# 4_Digitrol.net
KiCad netlist of a schematic drawn in Altium Designer
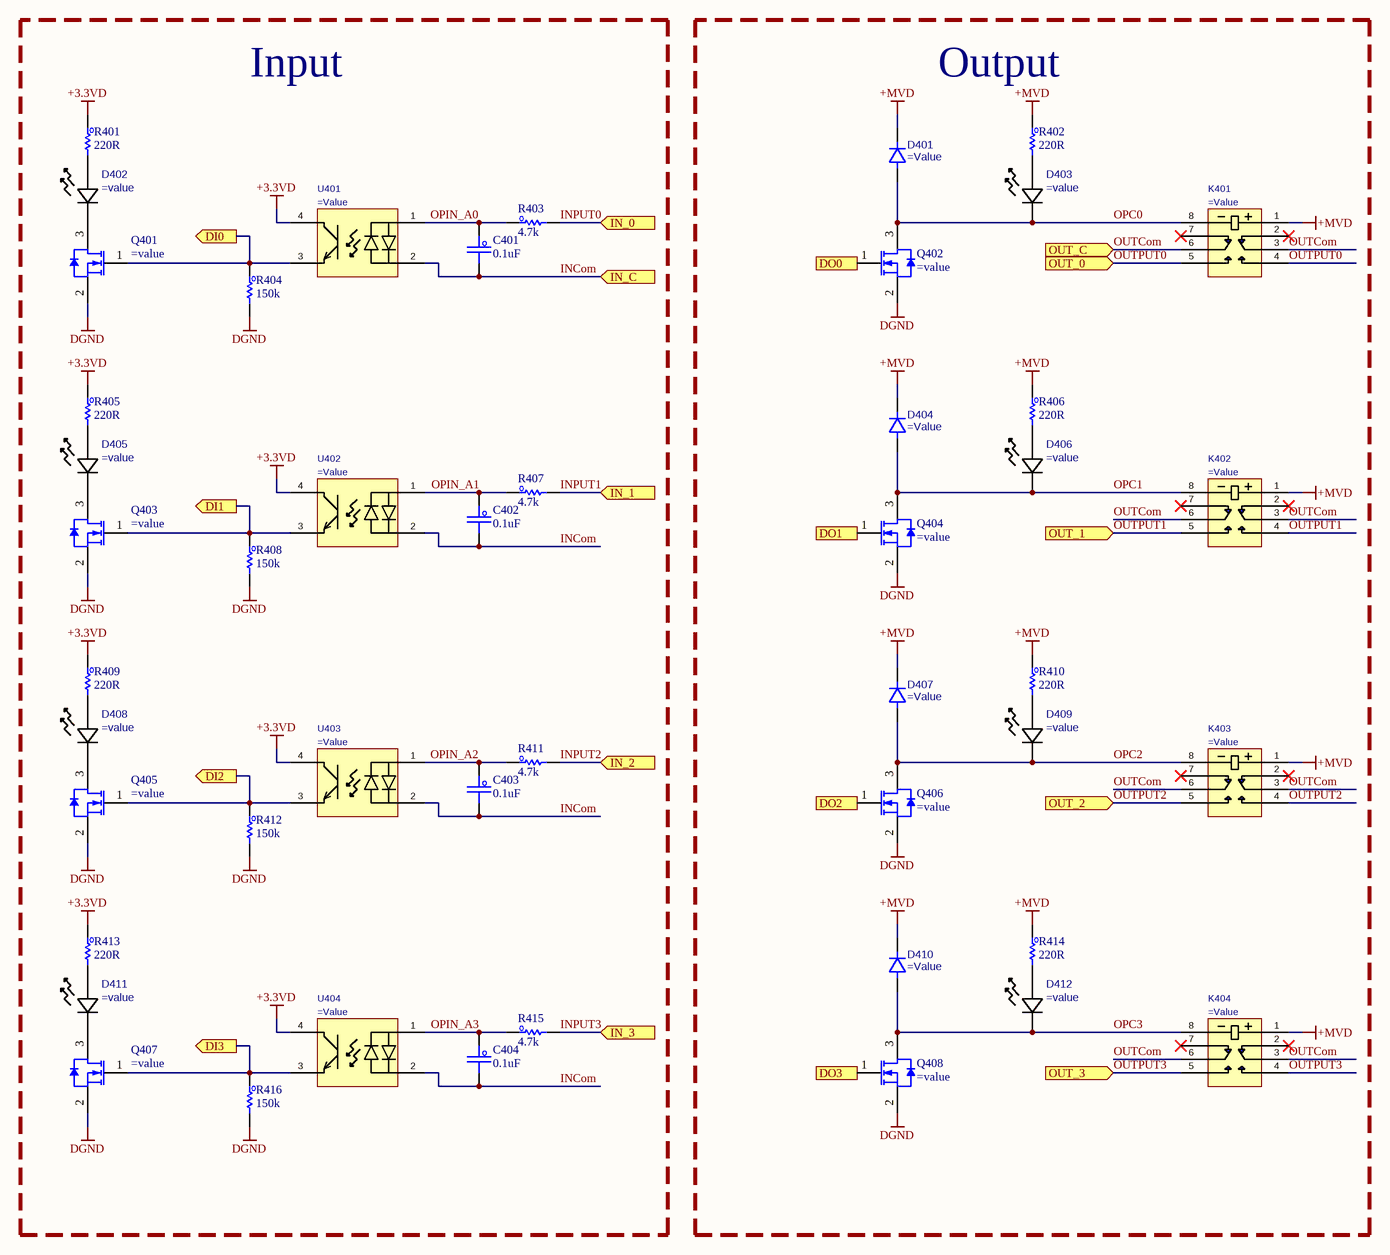
[diagram p0: 4_Digitrol.SchDoc]

(export (version "E")
  (design (tool "Eeschema 10.0.6"))
  (components
    (comp (ref "C401")
      (value "0.1uF")
      (footprint "C_0603")
      (description "CAP CER 0.1UF 50V X7R 0603")
      (fields (field (name "MANUFACTURER") "KEMET") (field (name "PARTNUMBER") "C0603C104K5RACTU"))
      (libsource (lib "UUSymbol") (part "C_Capacitor"))
    )
    (comp (ref "C402")
      (value "0.1uF")
      (footprint "C_0603")
      (description "CAP CER 0.1UF 50V X7R 0603")
      (fields (field (name "MANUFACTURER") "KEMET") (field (name "PARTNUMBER") "C0603C104K5RACTU"))
      (libsource (lib "UUSymbol") (part "C_Capacitor"))
    )
    (comp (ref "C403")
      (value "0.1uF")
      (footprint "C_0603")
      (description "CAP CER 0.1UF 50V X7R 0603")
      (fields (field (name "MANUFACTURER") "KEMET") (field (name "PARTNUMBER") "C0603C104K5RACTU"))
      (libsource (lib "UUSymbol") (part "C_Capacitor"))
    )
    (comp (ref "C404")
      (value "0.1uF")
      (footprint "C_0603")
      (description "CAP CER 0.1UF 50V X7R 0603")
      (fields (field (name "MANUFACTURER") "KEMET") (field (name "PARTNUMBER") "C0603C104K5RACTU"))
      (libsource (lib "UUSymbol") (part "C_Capacitor"))
    )
    (comp (ref "D401")
      (value "~")
      (footprint "SOD323")
      (description "DIODE SCHOTTKY 40V 2A 0603")
      (fields (field (name "MANUFACTURER") "Slkor(SLKORMICRO Elec.)") (field (name "PARTNUMBER") "SD103AWS"))
      (libsource (lib "UUSymbol") (part "D_PW_SD103AWS"))
    )
    (comp (ref "D402")
      (value "~")
      (footprint "LED_0VS75000_WRE")
      (description "LED BLUE CLEAR 0603 SMD")
      (fields (field (name "MANUFACTURER") "Wurth Electronics") (field (name "PARTNUMBER") "150060VS75000"))
      (libsource (lib "UUSymbol") (part "D_LED_150060BS75000"))
    )
    (comp (ref "D403")
      (value "~")
      (footprint "LED_0VS75000_WRE")
      (description "LED BLUE CLEAR 0603 SMD")
      (fields (field (name "MANUFACTURER") "Wurth Electronics") (field (name "PARTNUMBER") "150060VS75000"))
      (libsource (lib "UUSymbol") (part "D_LED_150060BS75000"))
    )
    (comp (ref "D404")
      (value "~")
      (footprint "SOD323")
      (description "DIODE SCHOTTKY 40V 2A 0603")
      (fields (field (name "MANUFACTURER") "Slkor(SLKORMICRO Elec.)") (field (name "PARTNUMBER") "SD103AWS"))
      (libsource (lib "UUSymbol") (part "D_PW_SD103AWS"))
    )
    (comp (ref "D405")
      (value "~")
      (footprint "LED_0VS75000_WRE")
      (description "LED BLUE CLEAR 0603 SMD")
      (fields (field (name "MANUFACTURER") "Wurth Electronics") (field (name "PARTNUMBER") "150060VS75000"))
      (libsource (lib "UUSymbol") (part "D_LED_150060BS75000"))
    )
    (comp (ref "D406")
      (value "~")
      (footprint "LED_0VS75000_WRE")
      (description "LED BLUE CLEAR 0603 SMD")
      (fields (field (name "MANUFACTURER") "Wurth Electronics") (field (name "PARTNUMBER") "150060VS75000"))
      (libsource (lib "UUSymbol") (part "D_LED_150060BS75000"))
    )
    (comp (ref "D407")
      (value "~")
      (footprint "SOD323")
      (description "DIODE SCHOTTKY 40V 2A 0603")
      (fields (field (name "MANUFACTURER") "Slkor(SLKORMICRO Elec.)") (field (name "PARTNUMBER") "SD103AWS"))
      (libsource (lib "UUSymbol") (part "D_PW_SD103AWS"))
    )
    (comp (ref "D408")
      (value "~")
      (footprint "LED_0VS75000_WRE")
      (description "LED BLUE CLEAR 0603 SMD")
      (fields (field (name "MANUFACTURER") "Wurth Electronics") (field (name "PARTNUMBER") "150060VS75000"))
      (libsource (lib "UUSymbol") (part "D_LED_150060BS75000"))
    )
    (comp (ref "D409")
      (value "~")
      (footprint "LED_0VS75000_WRE")
      (description "LED BLUE CLEAR 0603 SMD")
      (fields (field (name "MANUFACTURER") "Wurth Electronics") (field (name "PARTNUMBER") "150060VS75000"))
      (libsource (lib "UUSymbol") (part "D_LED_150060BS75000"))
    )
    (comp (ref "D410")
      (value "~")
      (footprint "SOD323")
      (description "DIODE SCHOTTKY 40V 2A 0603")
      (fields (field (name "MANUFACTURER") "Slkor(SLKORMICRO Elec.)") (field (name "PARTNUMBER") "SD103AWS"))
      (libsource (lib "UUSymbol") (part "D_PW_SD103AWS"))
    )
    (comp (ref "D411")
      (value "~")
      (footprint "LED_0VS75000_WRE")
      (description "LED BLUE CLEAR 0603 SMD")
      (fields (field (name "MANUFACTURER") "Wurth Electronics") (field (name "PARTNUMBER") "150060VS75000"))
      (libsource (lib "UUSymbol") (part "D_LED_150060BS75000"))
    )
    (comp (ref "D412")
      (value "~")
      (footprint "LED_0VS75000_WRE")
      (description "LED BLUE CLEAR 0603 SMD")
      (fields (field (name "MANUFACTURER") "Wurth Electronics") (field (name "PARTNUMBER") "150060VS75000"))
      (libsource (lib "UUSymbol") (part "D_LED_150060BS75000"))
    )
    (comp (ref "K401")
      (value "~")
      (footprint "RELAY_HFD4/12-SR")
      (description "Telecom Non Latching 12VDC DPDT SMD Relays RoHS")
      (fields
        (field (name "MANUFACTURER") "Xiamen Hongfa Electroacoustic")
        (field (name "PARTNUMBER") "HFD4/5-SR")
      )
      (libsource (lib "UUSymbol") (part "SW_RELAY_HFD4/12-SR"))
    )
    (comp (ref "K402")
      (value "~")
      (footprint "RELAY_HFD4/12-SR")
      (description "Telecom Non Latching 12VDC DPDT SMD Relays RoHS")
      (fields
        (field (name "MANUFACTURER") "Xiamen Hongfa Electroacoustic")
        (field (name "PARTNUMBER") "HFD4/5-SR")
      )
      (libsource (lib "UUSymbol") (part "SW_RELAY_HFD4/12-SR"))
    )
    (comp (ref "K403")
      (value "~")
      (footprint "RELAY_HFD4/12-SR")
      (description "Telecom Non Latching 12VDC DPDT SMD Relays RoHS")
      (fields
        (field (name "MANUFACTURER") "Xiamen Hongfa Electroacoustic")
        (field (name "PARTNUMBER") "HFD4/5-SR")
      )
      (libsource (lib "UUSymbol") (part "SW_RELAY_HFD4/12-SR"))
    )
    (comp (ref "K404")
      (value "~")
      (footprint "RELAY_HFD4/12-SR")
      (description "Telecom Non Latching 12VDC DPDT SMD Relays RoHS")
      (fields
        (field (name "MANUFACTURER") "Xiamen Hongfa Electroacoustic")
        (field (name "PARTNUMBER") "HFD4/5-SR")
      )
      (libsource (lib "UUSymbol") (part "SW_RELAY_HFD4/12-SR"))
    )
    (comp (ref "Q401")
      (value "~")
      (footprint "TRANS_CSD25481F4")
      (description "MOSFET N-CH 30V 2.3A 3PICOSTAR")
      (fields (field (name "MANUFACTURER") "Texas Instruments") (field (name "PARTNUMBER") "CSD17382F4"))
      (libsource (lib "UUSymbol") (part "Q_NMOS_CSD17382F4"))
    )
    (comp (ref "Q402")
      (value "~")
      (footprint "TRANS_CSD25481F4")
      (description "MOSFET N-CH 30V 2.3A 3PICOSTAR")
      (fields (field (name "MANUFACTURER") "Texas Instruments") (field (name "PARTNUMBER") "CSD17382F4"))
      (libsource (lib "UUSymbol") (part "Q_NMOS_CSD17382F4"))
    )
    (comp (ref "Q403")
      (value "~")
      (footprint "TRANS_CSD25481F4")
      (description "MOSFET N-CH 30V 2.3A 3PICOSTAR")
      (fields (field (name "MANUFACTURER") "Texas Instruments") (field (name "PARTNUMBER") "CSD17382F4"))
      (libsource (lib "UUSymbol") (part "Q_NMOS_CSD17382F4"))
    )
    (comp (ref "Q404")
      (value "~")
      (footprint "TRANS_CSD25481F4")
      (description "MOSFET N-CH 30V 2.3A 3PICOSTAR")
      (fields (field (name "MANUFACTURER") "Texas Instruments") (field (name "PARTNUMBER") "CSD17382F4"))
      (libsource (lib "UUSymbol") (part "Q_NMOS_CSD17382F4"))
    )
    (comp (ref "Q405")
      (value "~")
      (footprint "TRANS_CSD25481F4")
      (description "MOSFET N-CH 30V 2.3A 3PICOSTAR")
      (fields (field (name "MANUFACTURER") "Texas Instruments") (field (name "PARTNUMBER") "CSD17382F4"))
      (libsource (lib "UUSymbol") (part "Q_NMOS_CSD17382F4"))
    )
    (comp (ref "Q406")
      (value "~")
      (footprint "TRANS_CSD25481F4")
      (description "MOSFET N-CH 30V 2.3A 3PICOSTAR")
      (fields (field (name "MANUFACTURER") "Texas Instruments") (field (name "PARTNUMBER") "CSD17382F4"))
      (libsource (lib "UUSymbol") (part "Q_NMOS_CSD17382F4"))
    )
    (comp (ref "Q407")
      (value "~")
      (footprint "TRANS_CSD25481F4")
      (description "MOSFET N-CH 30V 2.3A 3PICOSTAR")
      (fields (field (name "MANUFACTURER") "Texas Instruments") (field (name "PARTNUMBER") "CSD17382F4"))
      (libsource (lib "UUSymbol") (part "Q_NMOS_CSD17382F4"))
    )
    (comp (ref "Q408")
      (value "~")
      (footprint "TRANS_CSD25481F4")
      (description "MOSFET N-CH 30V 2.3A 3PICOSTAR")
      (fields (field (name "MANUFACTURER") "Texas Instruments") (field (name "PARTNUMBER") "CSD17382F4"))
      (libsource (lib "UUSymbol") (part "Q_NMOS_CSD17382F4"))
    )
    (comp (ref "R401")
      (value "220R")
      (footprint "R_0603")
      (description "RES SMD 220 OHM 1% 1/10W 0603")
      (fields (field (name "MANUFACTURER") "Vishay Dale") (field (name "PARTNUMBER") "CRCW0603220RFKEAC"))
      (libsource (lib "UUSymbol") (part "R_Resister"))
    )
    (comp (ref "R402")
      (value "220R")
      (footprint "R_0603")
      (description "RES SMD 220 OHM 1% 1/10W 0603")
      (fields (field (name "MANUFACTURER") "Vishay Dale") (field (name "PARTNUMBER") "CRCW0603220RFKEAC"))
      (libsource (lib "UUSymbol") (part "R_Resister"))
    )
    (comp (ref "R403")
      (value "4.7k")
      (footprint "R_0603")
      (description "RES 4.7K OHM 5% 1/10W 0603")
      (fields (field (name "MANUFACTURER") "Vishay Dale") (field (name "PARTNUMBER") "CRCW06034K70JNEBC"))
      (libsource (lib "UUSymbol") (part "R_Resister"))
    )
    (comp (ref "R404")
      (value "150k")
      (footprint "R_0603")
      (description "RES SMD 150K OHM 1% 1/10W 0603")
      (fields (field (name "MANUFACTURER") "Vishay Dale") (field (name "PARTNUMBER") "CRCW0603150KFKEAC"))
      (libsource (lib "UUSymbol") (part "R_Resister"))
    )
    (comp (ref "R405")
      (value "220R")
      (footprint "R_0603")
      (description "RES SMD 220 OHM 1% 1/10W 0603")
      (fields (field (name "MANUFACTURER") "Vishay Dale") (field (name "PARTNUMBER") "CRCW0603220RFKEAC"))
      (libsource (lib "UUSymbol") (part "R_Resister"))
    )
    (comp (ref "R406")
      (value "220R")
      (footprint "R_0603")
      (description "RES SMD 220 OHM 1% 1/10W 0603")
      (fields (field (name "MANUFACTURER") "Vishay Dale") (field (name "PARTNUMBER") "CRCW0603220RFKEAC"))
      (libsource (lib "UUSymbol") (part "R_Resister"))
    )
    (comp (ref "R407")
      (value "4.7k")
      (footprint "R_0603")
      (description "RES 4.7K OHM 5% 1/10W 0603")
      (fields (field (name "MANUFACTURER") "Vishay Dale") (field (name "PARTNUMBER") "CRCW06034K70JNEBC"))
      (libsource (lib "UUSymbol") (part "R_Resister"))
    )
    (comp (ref "R408")
      (value "150k")
      (footprint "R_0603")
      (description "RES SMD 150K OHM 1% 1/10W 0603")
      (fields (field (name "MANUFACTURER") "Vishay Dale") (field (name "PARTNUMBER") "CRCW0603150KFKEAC"))
      (libsource (lib "UUSymbol") (part "R_Resister"))
    )
    (comp (ref "R409")
      (value "220R")
      (footprint "R_0603")
      (description "RES SMD 220 OHM 1% 1/10W 0603")
      (fields (field (name "MANUFACTURER") "Vishay Dale") (field (name "PARTNUMBER") "CRCW0603220RFKEAC"))
      (libsource (lib "UUSymbol") (part "R_Resister"))
    )
    (comp (ref "R410")
      (value "220R")
      (footprint "R_0603")
      (description "RES SMD 220 OHM 1% 1/10W 0603")
      (fields (field (name "MANUFACTURER") "Vishay Dale") (field (name "PARTNUMBER") "CRCW0603220RFKEAC"))
      (libsource (lib "UUSymbol") (part "R_Resister"))
    )
    (comp (ref "R411")
      (value "4.7k")
      (footprint "R_0603")
      (description "RES 4.7K OHM 5% 1/10W 0603")
      (fields (field (name "MANUFACTURER") "Vishay Dale") (field (name "PARTNUMBER") "CRCW06034K70JNEBC"))
      (libsource (lib "UUSymbol") (part "R_Resister"))
    )
    (comp (ref "R412")
      (value "150k")
      (footprint "R_0603")
      (description "RES SMD 150K OHM 1% 1/10W 0603")
      (fields (field (name "MANUFACTURER") "Vishay Dale") (field (name "PARTNUMBER") "CRCW0603150KFKEAC"))
      (libsource (lib "UUSymbol") (part "R_Resister"))
    )
    (comp (ref "R413")
      (value "220R")
      (footprint "R_0603")
      (description "RES SMD 220 OHM 1% 1/10W 0603")
      (fields (field (name "MANUFACTURER") "Vishay Dale") (field (name "PARTNUMBER") "CRCW0603220RFKEAC"))
      (libsource (lib "UUSymbol") (part "R_Resister"))
    )
    (comp (ref "R414")
      (value "220R")
      (footprint "R_0603")
      (description "RES SMD 220 OHM 1% 1/10W 0603")
      (fields (field (name "MANUFACTURER") "Vishay Dale") (field (name "PARTNUMBER") "CRCW0603220RFKEAC"))
      (libsource (lib "UUSymbol") (part "R_Resister"))
    )
    (comp (ref "R415")
      (value "4.7k")
      (footprint "R_0603")
      (description "RES 4.7K OHM 5% 1/10W 0603")
      (fields (field (name "MANUFACTURER") "Vishay Dale") (field (name "PARTNUMBER") "CRCW06034K70JNEBC"))
      (libsource (lib "UUSymbol") (part "R_Resister"))
    )
    (comp (ref "R416")
      (value "150k")
      (footprint "R_0603")
      (description "RES SMD 150K OHM 1% 1/10W 0603")
      (fields (field (name "MANUFACTURER") "Vishay Dale") (field (name "PARTNUMBER") "CRCW0603150KFKEAC"))
      (libsource (lib "UUSymbol") (part "R_Resister"))
    )
    (comp (ref "U401")
      (value "~")
      (footprint "SOIC_M618A-3T_VI")
      (description "OPTOISOLATR 5KV TRANSISTOR 4-SMD")
      (fields (field (name "MANUFACTURER") "Lite-On Inc.") (field (name "PARTNUMBER") "LTV-814S-TA1"))
      (libsource (lib "UUSymbol") (part "IC_OPTO_LTV-814S-TA1"))
    )
    (comp (ref "U402")
      (value "~")
      (footprint "SOIC_M618A-3T_VI")
      (description "OPTOISOLATR 5KV TRANSISTOR 4-SMD")
      (fields (field (name "MANUFACTURER") "Lite-On Inc.") (field (name "PARTNUMBER") "LTV-814S-TA1"))
      (libsource (lib "UUSymbol") (part "IC_OPTO_LTV-814S-TA1"))
    )
    (comp (ref "U403")
      (value "~")
      (footprint "SOIC_M618A-3T_VI")
      (description "OPTOISOLATR 5KV TRANSISTOR 4-SMD")
      (fields (field (name "MANUFACTURER") "Lite-On Inc.") (field (name "PARTNUMBER") "LTV-814S-TA1"))
      (libsource (lib "UUSymbol") (part "IC_OPTO_LTV-814S-TA1"))
    )
    (comp (ref "U404")
      (value "~")
      (footprint "SOIC_M618A-3T_VI")
      (description "OPTOISOLATR 5KV TRANSISTOR 4-SMD")
      (fields (field (name "MANUFACTURER") "Lite-On Inc.") (field (name "PARTNUMBER") "LTV-814S-TA1"))
      (libsource (lib "UUSymbol") (part "IC_OPTO_LTV-814S-TA1"))
    )
  )
  (nets
    (net (code "1") (name "+3.3VD") (class "Default")
      (node (ref "R401") (pin "1") (pinfunction "1_1") (pintype "passive"))
      (node (ref "R405") (pin "1") (pinfunction "1_1") (pintype "passive"))
      (node (ref "R409") (pin "1") (pinfunction "1_1") (pintype "passive"))
      (node (ref "R413") (pin "1") (pinfunction "1_1") (pintype "passive"))
      (node (ref "U401") (pin "4") (pinfunction "C_4") (pintype "passive"))
      (node (ref "U402") (pin "4") (pinfunction "C_4") (pintype "passive"))
      (node (ref "U403") (pin "4") (pinfunction "C_4") (pintype "passive"))
      (node (ref "U404") (pin "4") (pinfunction "C_4") (pintype "passive"))
    )
    (net (code "2") (name "+MVD") (class "Default")
      (node (ref "D401") (pin "1") (pinfunction "1_1") (pintype "passive"))
      (node (ref "D404") (pin "1") (pinfunction "1_1") (pintype "passive"))
      (node (ref "D407") (pin "1") (pinfunction "1_1") (pintype "passive"))
      (node (ref "D410") (pin "1") (pinfunction "1_1") (pintype "passive"))
      (node (ref "K401") (pin "1") (pinfunction "1_1") (pintype "passive"))
      (node (ref "K402") (pin "1") (pinfunction "1_1") (pintype "passive"))
      (node (ref "K403") (pin "1") (pinfunction "1_1") (pintype "passive"))
      (node (ref "K404") (pin "1") (pinfunction "1_1") (pintype "passive"))
      (node (ref "R402") (pin "1") (pinfunction "1_1") (pintype "passive"))
      (node (ref "R406") (pin "1") (pinfunction "1_1") (pintype "passive"))
      (node (ref "R410") (pin "1") (pinfunction "1_1") (pintype "passive"))
      (node (ref "R414") (pin "1") (pinfunction "1_1") (pintype "passive"))
    )
    (net (code "3") (name "/DI0") (class "Default")
      (node (ref "Q401") (pin "1") (pinfunction "G_1") (pintype "passive"))
      (node (ref "R404") (pin "1") (pinfunction "1_1") (pintype "passive"))
      (node (ref "U401") (pin "3") (pinfunction "E_3") (pintype "passive"))
    )
    (net (code "4") (name "/DI1") (class "Default")
      (node (ref "Q403") (pin "1") (pinfunction "G_1") (pintype "passive"))
      (node (ref "R408") (pin "1") (pinfunction "1_1") (pintype "passive"))
      (node (ref "U402") (pin "3") (pinfunction "E_3") (pintype "passive"))
    )
    (net (code "5") (name "/DI2") (class "Default")
      (node (ref "Q405") (pin "1") (pinfunction "G_1") (pintype "passive"))
      (node (ref "R412") (pin "1") (pinfunction "1_1") (pintype "passive"))
      (node (ref "U403") (pin "3") (pinfunction "E_3") (pintype "passive"))
    )
    (net (code "6") (name "/DI3") (class "Default")
      (node (ref "Q407") (pin "1") (pinfunction "G_1") (pintype "passive"))
      (node (ref "R416") (pin "1") (pinfunction "1_1") (pintype "passive"))
      (node (ref "U404") (pin "3") (pinfunction "E_3") (pintype "passive"))
    )
    (net (code "7") (name "/DO0") (class "Default")
      (node (ref "Q402") (pin "1") (pinfunction "G_1") (pintype "passive"))
    )
    (net (code "8") (name "/DO1") (class "Default")
      (node (ref "Q404") (pin "1") (pinfunction "G_1") (pintype "passive"))
    )
    (net (code "9") (name "/DO2") (class "Default")
      (node (ref "Q406") (pin "1") (pinfunction "G_1") (pintype "passive"))
    )
    (net (code "10") (name "/DO3") (class "Default")
      (node (ref "Q408") (pin "1") (pinfunction "G_1") (pintype "passive"))
    )
    (net (code "11") (name "/INCom") (class "Default")
      (node (ref "C401") (pin "2") (pinfunction "2_2") (pintype "passive"))
      (node (ref "C402") (pin "2") (pinfunction "2_2") (pintype "passive"))
      (node (ref "C403") (pin "2") (pinfunction "2_2") (pintype "passive"))
      (node (ref "C404") (pin "2") (pinfunction "2_2") (pintype "passive"))
      (node (ref "U401") (pin "2") (pinfunction "C_2_2") (pintype "passive"))
      (node (ref "U402") (pin "2") (pinfunction "C_2_2") (pintype "passive"))
      (node (ref "U403") (pin "2") (pinfunction "C_2_2") (pintype "passive"))
      (node (ref "U404") (pin "2") (pinfunction "C_2_2") (pintype "passive"))
    )
    (net (code "12") (name "/INPUT0") (class "Default")
      (node (ref "R403") (pin "2") (pinfunction "2_2") (pintype "passive"))
    )
    (net (code "13") (name "/INPUT1") (class "Default")
      (node (ref "R407") (pin "2") (pinfunction "2_2") (pintype "passive"))
    )
    (net (code "14") (name "/INPUT2") (class "Default")
      (node (ref "R411") (pin "2") (pinfunction "2_2") (pintype "passive"))
    )
    (net (code "15") (name "/INPUT3") (class "Default")
      (node (ref "R415") (pin "2") (pinfunction "2_2") (pintype "passive"))
    )
    (net (code "16") (name "/OPC0") (class "Default")
      (node (ref "D401") (pin "2") (pinfunction "2_2") (pintype "passive"))
      (node (ref "D403") (pin "1") (pinfunction "1_1") (pintype "passive"))
      (node (ref "K401") (pin "8") (pinfunction "8_8") (pintype "passive"))
      (node (ref "Q402") (pin "3") (pinfunction "D_3") (pintype "passive"))
    )
    (net (code "17") (name "/OPC1") (class "Default")
      (node (ref "D404") (pin "2") (pinfunction "2_2") (pintype "passive"))
      (node (ref "D406") (pin "1") (pinfunction "1_1") (pintype "passive"))
      (node (ref "K402") (pin "8") (pinfunction "8_8") (pintype "passive"))
      (node (ref "Q404") (pin "3") (pinfunction "D_3") (pintype "passive"))
    )
    (net (code "18") (name "/OPC2") (class "Default")
      (node (ref "D407") (pin "2") (pinfunction "2_2") (pintype "passive"))
      (node (ref "D409") (pin "1") (pinfunction "1_1") (pintype "passive"))
      (node (ref "K403") (pin "8") (pinfunction "8_8") (pintype "passive"))
      (node (ref "Q406") (pin "3") (pinfunction "D_3") (pintype "passive"))
    )
    (net (code "19") (name "/OPC3") (class "Default")
      (node (ref "D410") (pin "2") (pinfunction "2_2") (pintype "passive"))
      (node (ref "D412") (pin "1") (pinfunction "1_1") (pintype "passive"))
      (node (ref "K404") (pin "8") (pinfunction "8_8") (pintype "passive"))
      (node (ref "Q408") (pin "3") (pinfunction "D_3") (pintype "passive"))
    )
    (net (code "20") (name "/OPIN_A0") (class "Default")
      (node (ref "C401") (pin "1") (pinfunction "1_1") (pintype "passive"))
      (node (ref "R403") (pin "1") (pinfunction "1_1") (pintype "passive"))
      (node (ref "U401") (pin "1") (pinfunction "A_1") (pintype "passive"))
    )
    (net (code "21") (name "/OPIN_A1") (class "Default")
      (node (ref "C402") (pin "1") (pinfunction "1_1") (pintype "passive"))
      (node (ref "R407") (pin "1") (pinfunction "1_1") (pintype "passive"))
      (node (ref "U402") (pin "1") (pinfunction "A_1") (pintype "passive"))
    )
    (net (code "22") (name "/OPIN_A2") (class "Default")
      (node (ref "C403") (pin "1") (pinfunction "1_1") (pintype "passive"))
      (node (ref "R411") (pin "1") (pinfunction "1_1") (pintype "passive"))
      (node (ref "U403") (pin "1") (pinfunction "A_1") (pintype "passive"))
    )
    (net (code "23") (name "/OPIN_A3") (class "Default")
      (node (ref "C404") (pin "1") (pinfunction "1_1") (pintype "passive"))
      (node (ref "R415") (pin "1") (pinfunction "1_1") (pintype "passive"))
      (node (ref "U404") (pin "1") (pinfunction "A_1") (pintype "passive"))
    )
    (net (code "24") (name "/OUTCom") (class "Default")
      (node (ref "K401") (pin "3") (pinfunction "3_3") (pintype "passive"))
      (node (ref "K401") (pin "6") (pinfunction "6_6") (pintype "passive"))
      (node (ref "K402") (pin "3") (pinfunction "3_3") (pintype "passive"))
      (node (ref "K402") (pin "6") (pinfunction "6_6") (pintype "passive"))
      (node (ref "K403") (pin "3") (pinfunction "3_3") (pintype "passive"))
      (node (ref "K403") (pin "6") (pinfunction "6_6") (pintype "passive"))
      (node (ref "K404") (pin "3") (pinfunction "3_3") (pintype "passive"))
      (node (ref "K404") (pin "6") (pinfunction "6_6") (pintype "passive"))
    )
    (net (code "25") (name "/OUTPUT0") (class "Default")
      (node (ref "K401") (pin "4") (pinfunction "4_4") (pintype "passive"))
      (node (ref "K401") (pin "5") (pinfunction "5_5") (pintype "passive"))
    )
    (net (code "26") (name "/OUTPUT1") (class "Default")
      (node (ref "K402") (pin "4") (pinfunction "4_4") (pintype "passive"))
      (node (ref "K402") (pin "5") (pinfunction "5_5") (pintype "passive"))
    )
    (net (code "27") (name "/OUTPUT2") (class "Default")
      (node (ref "K403") (pin "4") (pinfunction "4_4") (pintype "passive"))
      (node (ref "K403") (pin "5") (pinfunction "5_5") (pintype "passive"))
    )
    (net (code "28") (name "/OUTPUT3") (class "Default")
      (node (ref "K404") (pin "4") (pinfunction "4_4") (pintype "passive"))
      (node (ref "K404") (pin "5") (pinfunction "5_5") (pintype "passive"))
    )
    (net (code "29") (name "DGND") (class "Default")
      (node (ref "Q401") (pin "2") (pinfunction "S_2") (pintype "passive"))
      (node (ref "Q402") (pin "2") (pinfunction "S_2") (pintype "passive"))
      (node (ref "Q403") (pin "2") (pinfunction "S_2") (pintype "passive"))
      (node (ref "Q404") (pin "2") (pinfunction "S_2") (pintype "passive"))
      (node (ref "Q405") (pin "2") (pinfunction "S_2") (pintype "passive"))
      (node (ref "Q406") (pin "2") (pinfunction "S_2") (pintype "passive"))
      (node (ref "Q407") (pin "2") (pinfunction "S_2") (pintype "passive"))
      (node (ref "Q408") (pin "2") (pinfunction "S_2") (pintype "passive"))
      (node (ref "R404") (pin "2") (pinfunction "2_2") (pintype "passive"))
      (node (ref "R408") (pin "2") (pinfunction "2_2") (pintype "passive"))
      (node (ref "R412") (pin "2") (pinfunction "2_2") (pintype "passive"))
      (node (ref "R416") (pin "2") (pinfunction "2_2") (pintype "passive"))
    )
    (net (code "30") (name "Net-(D402-Pad2)") (class "Default")
      (node (ref "D402") (pin "2") (pinfunction "2_2") (pintype "passive"))
      (node (ref "R401") (pin "2") (pinfunction "2_2") (pintype "passive"))
    )
    (net (code "31") (name "Net-(D403-Pad2)") (class "Default")
      (node (ref "D403") (pin "2") (pinfunction "2_2") (pintype "passive"))
      (node (ref "R402") (pin "2") (pinfunction "2_2") (pintype "passive"))
    )
    (net (code "32") (name "Net-(D405-Pad2)") (class "Default")
      (node (ref "D405") (pin "2") (pinfunction "2_2") (pintype "passive"))
      (node (ref "R405") (pin "2") (pinfunction "2_2") (pintype "passive"))
    )
    (net (code "33") (name "Net-(D406-Pad2)") (class "Default")
      (node (ref "D406") (pin "2") (pinfunction "2_2") (pintype "passive"))
      (node (ref "R406") (pin "2") (pinfunction "2_2") (pintype "passive"))
    )
    (net (code "34") (name "Net-(D408-Pad2)") (class "Default")
      (node (ref "D408") (pin "2") (pinfunction "2_2") (pintype "passive"))
      (node (ref "R409") (pin "2") (pinfunction "2_2") (pintype "passive"))
    )
    (net (code "35") (name "Net-(D409-Pad2)") (class "Default")
      (node (ref "D409") (pin "2") (pinfunction "2_2") (pintype "passive"))
      (node (ref "R410") (pin "2") (pinfunction "2_2") (pintype "passive"))
    )
    (net (code "36") (name "Net-(D411-Pad2)") (class "Default")
      (node (ref "D411") (pin "2") (pinfunction "2_2") (pintype "passive"))
      (node (ref "R413") (pin "2") (pinfunction "2_2") (pintype "passive"))
    )
    (net (code "37") (name "Net-(D412-Pad2)") (class "Default")
      (node (ref "D412") (pin "2") (pinfunction "2_2") (pintype "passive"))
      (node (ref "R414") (pin "2") (pinfunction "2_2") (pintype "passive"))
    )
    (net (code "38") (name "Net-(Q401-D)") (class "Default")
      (node (ref "D402") (pin "1") (pinfunction "1_1") (pintype "passive"))
      (node (ref "Q401") (pin "3") (pinfunction "D_3") (pintype "passive"))
    )
    (net (code "39") (name "Net-(Q403-D)") (class "Default")
      (node (ref "D405") (pin "1") (pinfunction "1_1") (pintype "passive"))
      (node (ref "Q403") (pin "3") (pinfunction "D_3") (pintype "passive"))
    )
    (net (code "40") (name "Net-(Q405-D)") (class "Default")
      (node (ref "D408") (pin "1") (pinfunction "1_1") (pintype "passive"))
      (node (ref "Q405") (pin "3") (pinfunction "D_3") (pintype "passive"))
    )
    (net (code "41") (name "Net-(Q407-D)") (class "Default")
      (node (ref "D411") (pin "1") (pinfunction "1_1") (pintype "passive"))
      (node (ref "Q407") (pin "3") (pinfunction "D_3") (pintype "passive"))
    )
    (net (code "42") (name "unconnected-(K401-Pad2)") (class "Default")
      (node (ref "K401") (pin "2") (pinfunction "2_2") (pintype "passive+no_connect"))
    )
    (net (code "43") (name "unconnected-(K401-Pad7)") (class "Default")
      (node (ref "K401") (pin "7") (pinfunction "7_7") (pintype "passive+no_connect"))
    )
    (net (code "44") (name "unconnected-(K402-Pad2)") (class "Default")
      (node (ref "K402") (pin "2") (pinfunction "2_2") (pintype "passive+no_connect"))
    )
    (net (code "45") (name "unconnected-(K402-Pad7)") (class "Default")
      (node (ref "K402") (pin "7") (pinfunction "7_7") (pintype "passive+no_connect"))
    )
    (net (code "46") (name "unconnected-(K403-Pad2)") (class "Default")
      (node (ref "K403") (pin "2") (pinfunction "2_2") (pintype "passive+no_connect"))
    )
    (net (code "47") (name "unconnected-(K403-Pad7)") (class "Default")
      (node (ref "K403") (pin "7") (pinfunction "7_7") (pintype "passive+no_connect"))
    )
    (net (code "48") (name "unconnected-(K404-Pad2)") (class "Default")
      (node (ref "K404") (pin "2") (pinfunction "2_2") (pintype "passive+no_connect"))
    )
    (net (code "49") (name "unconnected-(K404-Pad7)") (class "Default")
      (node (ref "K404") (pin "7") (pinfunction "7_7") (pintype "passive+no_connect"))
    )
  )
)
